# PIRSN_v1.net
KiCad netlist of a schematic drawn in EAGLE
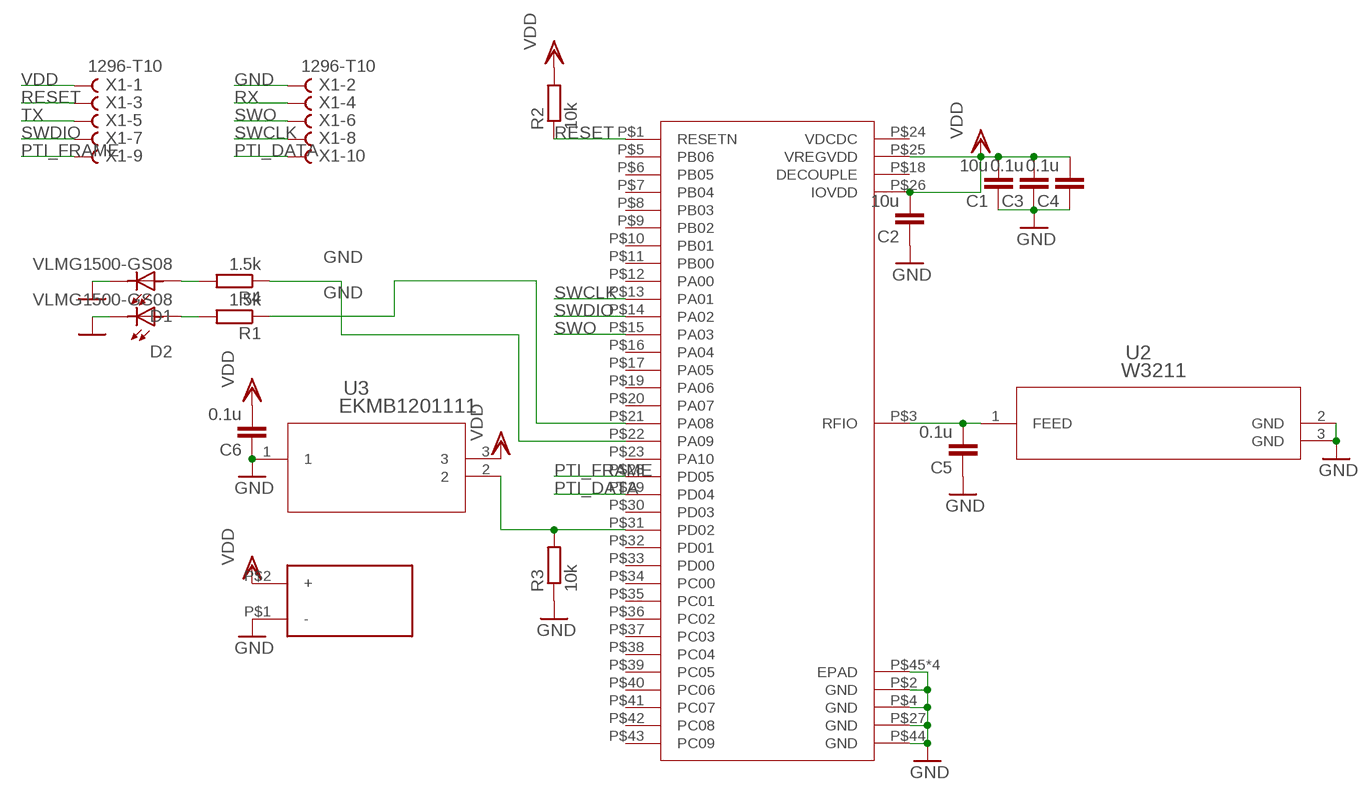
[diagram p0: schematic, sheet 1]

(export (version "E")
  (design (tool "Eeschema 10.0.6"))
  (components
    (comp (ref "C1")
      (value "10u")
      (footprint "eagle-import:C0603R")
      (libsource (lib "eagle-import") (part "CC0603R"))
    )
    (comp (ref "C2")
      (value "10u")
      (footprint "eagle-import:C0603R")
      (libsource (lib "eagle-import") (part "CC0603R"))
    )
    (comp (ref "C3")
      (value "0.1u")
      (footprint "eagle-import:C0402")
      (libsource (lib "eagle-import") (part "CC0402"))
    )
    (comp (ref "C4")
      (value "0.1u")
      (footprint "eagle-import:C0402")
      (libsource (lib "eagle-import") (part "CC0402"))
    )
    (comp (ref "C5")
      (value "0.1u")
      (footprint "eagle-import:C0402")
      (libsource (lib "eagle-import") (part "CC0402"))
    )
    (comp (ref "C6")
      (value "0.1u")
      (footprint "eagle-import:C0402")
      (libsource (lib "eagle-import") (part "CC0402"))
    )
    (comp (ref "D1")
      (value "VLMG1500-GS08")
      (footprint "eagle-import:LEDC1005X35N")
      (fields (field (name "MF") "Vishay"))
      (libsource (lib "eagle-import") (part "VLMG1500-GS08"))
    )
    (comp (ref "D2")
      (value "VLMG1500-GS08")
      (footprint "eagle-import:LEDC1005X35N")
      (fields (field (name "MF") "Vishay"))
      (libsource (lib "eagle-import") (part "VLMG1500-GS08"))
    )
    (comp (ref "R1")
      (value "1.5k")
      (footprint "eagle-import:R0402")
      (libsource (lib "eagle-import") (part "RR0402"))
    )
    (comp (ref "R2")
      (value "10k")
      (footprint "eagle-import:R0402")
      (libsource (lib "eagle-import") (part "RR0402"))
    )
    (comp (ref "R3")
      (value "10k")
      (footprint "eagle-import:R0402")
      (libsource (lib "eagle-import") (part "RR0402"))
    )
    (comp (ref "R4")
      (value "1.5k")
      (footprint "eagle-import:R0402")
      (libsource (lib "eagle-import") (part "RR0402"))
    )
    (comp (ref "U$1")
      (value "ZGM230S")
      (footprint "eagle-import:ZGM230S")
      (libsource (lib "eagle-import") (part "ZGM230S"))
    )
    (comp (ref "U$2")
      (value "BS-24R")
      (footprint "eagle-import:BS-24")
      (libsource (lib "eagle-import") (part "BS-24R"))
    )
    (comp (ref "U2")
      (value "W3211")
      (footprint "eagle-import:CHIP_3211_PUL")
      (fields (field (name "COPYRIGHT") "Copyright (C) 2022 Ultra Librarian. All rights reserved."))
      (libsource (lib "eagle-import") (part "W3211"))
    )
    (comp (ref "U3")
      (value "EKMB1201111")
      (footprint "eagle-import:SENSOR_B1201111_PAN")
      (fields (field (name "COPYRIGHT") "Copyright (C) 2022 Ultra Librarian. All rights reserved."))
      (libsource (lib "eagle-import") (part "EKMB1201111"))
    )
    (comp (ref "X1")
      (value "1296-T10")
      (footprint "eagle-import:1296-10")
      (libsource (lib "eagle-import") (part "1296-T10"))
    )
  )
  (nets
    (net (code "1") (name "/PTI_DATA") (class "Default")
      (node (ref "U$1") (pin "P$29") (pinfunction "PD04_P$29") (pintype "bidirectional"))
      (node (ref "X1") (pin "10") (pinfunction "B_10") (pintype "passive"))
    )
    (net (code "2") (name "/PTI_FRAME") (class "Default")
      (node (ref "U$1") (pin "P$28") (pinfunction "PD05_P$28") (pintype "bidirectional"))
      (node (ref "X1") (pin "9") (pinfunction "B_9") (pintype "passive"))
    )
    (net (code "3") (name "/RESET") (class "Default")
      (node (ref "R2") (pin "1") (pinfunction "1_1") (pintype "passive"))
      (node (ref "U$1") (pin "P$1") (pinfunction "RESETN_P$1") (pintype "bidirectional"))
      (node (ref "X1") (pin "3") (pinfunction "B_3") (pintype "passive"))
    )
    (net (code "4") (name "/RX") (class "Default")
      (node (ref "X1") (pin "4") (pinfunction "B_4") (pintype "passive"))
    )
    (net (code "5") (name "/SWCLK") (class "Default")
      (node (ref "U$1") (pin "P$13") (pinfunction "PA01_P$13") (pintype "bidirectional"))
      (node (ref "X1") (pin "8") (pinfunction "B_8") (pintype "passive"))
    )
    (net (code "6") (name "/SWDIO") (class "Default")
      (node (ref "U$1") (pin "P$14") (pinfunction "PA02_P$14") (pintype "bidirectional"))
      (node (ref "X1") (pin "7") (pinfunction "B_7") (pintype "passive"))
    )
    (net (code "7") (name "/SWO") (class "Default")
      (node (ref "U$1") (pin "P$15") (pinfunction "PA03_P$15") (pintype "bidirectional"))
      (node (ref "X1") (pin "6") (pinfunction "B_6") (pintype "passive"))
    )
    (net (code "8") (name "/TX") (class "Default")
      (node (ref "X1") (pin "5") (pinfunction "B_5") (pintype "passive"))
    )
    (net (code "9") (name "GND") (class "Default")
      (node (ref "C1") (pin "1") (pinfunction "1_1") (pintype "passive"))
      (node (ref "C2") (pin "1") (pinfunction "1_1") (pintype "passive"))
      (node (ref "C3") (pin "1") (pinfunction "1_1") (pintype "passive"))
      (node (ref "C4") (pin "1") (pinfunction "1_1") (pintype "passive"))
      (node (ref "C5") (pin "1") (pinfunction "1_1") (pintype "passive"))
      (node (ref "C6") (pin "1") (pinfunction "1_1") (pintype "passive"))
      (node (ref "D1") (pin "2") (pinfunction "2_2") (pintype "passive"))
      (node (ref "D2") (pin "2") (pinfunction "2_2") (pintype "passive"))
      (node (ref "R3") (pin "1") (pinfunction "1_1") (pintype "passive"))
      (node (ref "U$1") (pin "P$2") (pinfunction "GND_P$2") (pintype "bidirectional"))
      (node (ref "U$1") (pin "P$27") (pinfunction "GND_P$27") (pintype "bidirectional"))
      (node (ref "U$1") (pin "P$4") (pinfunction "GND_P$4") (pintype "bidirectional"))
      (node (ref "U$1") (pin "P$44") (pinfunction "GND_P$44") (pintype "bidirectional"))
      (node (ref "U$1") (pin "P$45") (pinfunction "EPAD_P$45") (pintype "bidirectional"))
      (node (ref "U$1") (pin "P$46") (pinfunction "EPAD_P$46") (pintype "bidirectional"))
      (node (ref "U$1") (pin "P$47") (pinfunction "EPAD_P$47") (pintype "bidirectional"))
      (node (ref "U$1") (pin "P$48") (pinfunction "EPAD_P$48") (pintype "bidirectional"))
      (node (ref "U$2") (pin "P$1") (pinfunction "-_P$1") (pintype "bidirectional"))
      (node (ref "U2") (pin "2") (pinfunction "GND_2") (pintype "passive"))
      (node (ref "U2") (pin "3") (pinfunction "GND_3") (pintype "passive"))
      (node (ref "U3") (pin "1") (pinfunction "1_1") (pintype "passive"))
      (node (ref "X1") (pin "2") (pinfunction "B_2") (pintype "passive"))
    )
    (net (code "10") (name "Net-(D1-Pad1)") (class "Default")
      (node (ref "D1") (pin "1") (pinfunction "1_1") (pintype "passive"))
      (node (ref "R4") (pin "2") (pinfunction "2_2") (pintype "passive"))
    )
    (net (code "11") (name "Net-(D2-Pad1)") (class "Default")
      (node (ref "D2") (pin "1") (pinfunction "1_1") (pintype "passive"))
      (node (ref "R1") (pin "2") (pinfunction "2_2") (pintype "passive"))
    )
    (net (code "12") (name "Net-(U$1-PA08)") (class "Default")
      (node (ref "R1") (pin "1") (pinfunction "1_1") (pintype "passive"))
      (node (ref "U$1") (pin "P$21") (pinfunction "PA08_P$21") (pintype "bidirectional"))
    )
    (net (code "13") (name "Net-(U$1-PA09)") (class "Default")
      (node (ref "R4") (pin "1") (pinfunction "1_1") (pintype "passive"))
      (node (ref "U$1") (pin "P$22") (pinfunction "PA09_P$22") (pintype "bidirectional"))
    )
    (net (code "14") (name "Net-(U$1-PD02)") (class "Default")
      (node (ref "R3") (pin "2") (pinfunction "2_2") (pintype "passive"))
      (node (ref "U$1") (pin "P$31") (pinfunction "PD02_P$31") (pintype "bidirectional"))
      (node (ref "U3") (pin "2") (pinfunction "2_2") (pintype "passive"))
    )
    (net (code "15") (name "Net-(U$1-RFIO)") (class "Default")
      (node (ref "C5") (pin "2") (pinfunction "2_2") (pintype "passive"))
      (node (ref "U$1") (pin "P$3") (pinfunction "RFIO_P$3") (pintype "bidirectional"))
      (node (ref "U2") (pin "1") (pinfunction "FEED_1") (pintype "passive"))
    )
    (net (code "16") (name "VDD") (class "Default")
      (node (ref "C1") (pin "2") (pinfunction "2_2") (pintype "passive"))
      (node (ref "C2") (pin "2") (pinfunction "2_2") (pintype "passive"))
      (node (ref "C3") (pin "2") (pinfunction "2_2") (pintype "passive"))
      (node (ref "C4") (pin "2") (pinfunction "2_2") (pintype "passive"))
      (node (ref "C6") (pin "2") (pinfunction "2_2") (pintype "passive"))
      (node (ref "R2") (pin "2") (pinfunction "2_2") (pintype "passive"))
      (node (ref "U$1") (pin "P$25") (pinfunction "VREGVDD_P$25") (pintype "bidirectional"))
      (node (ref "U$1") (pin "P$26") (pinfunction "IOVDD_P$26") (pintype "bidirectional"))
      (node (ref "U$2") (pin "P$2") (pinfunction "+_P$2") (pintype "bidirectional"))
      (node (ref "U3") (pin "3") (pinfunction "3_3") (pintype "passive"))
      (node (ref "X1") (pin "1") (pinfunction "B_1") (pintype "passive"))
    )
    (net (code "17") (name "unconnected-(U$1-DECOUPLE-PadP$18)") (class "Default")
      (node (ref "U$1") (pin "P$18") (pinfunction "DECOUPLE_P$18") (pintype "bidirectional"))
    )
    (net (code "18") (name "unconnected-(U$1-PA00-PadP$12)") (class "Default")
      (node (ref "U$1") (pin "P$12") (pinfunction "PA00_P$12") (pintype "bidirectional"))
    )
    (net (code "19") (name "unconnected-(U$1-PA04-PadP$16)") (class "Default")
      (node (ref "U$1") (pin "P$16") (pinfunction "PA04_P$16") (pintype "bidirectional"))
    )
    (net (code "20") (name "unconnected-(U$1-PA05-PadP$17)") (class "Default")
      (node (ref "U$1") (pin "P$17") (pinfunction "PA05_P$17") (pintype "bidirectional"))
    )
    (net (code "21") (name "unconnected-(U$1-PA06-PadP$19)") (class "Default")
      (node (ref "U$1") (pin "P$19") (pinfunction "PA06_P$19") (pintype "bidirectional"))
    )
    (net (code "22") (name "unconnected-(U$1-PA07-PadP$20)") (class "Default")
      (node (ref "U$1") (pin "P$20") (pinfunction "PA07_P$20") (pintype "bidirectional"))
    )
    (net (code "23") (name "unconnected-(U$1-PA10-PadP$23)") (class "Default")
      (node (ref "U$1") (pin "P$23") (pinfunction "PA10_P$23") (pintype "bidirectional"))
    )
    (net (code "24") (name "unconnected-(U$1-PB00-PadP$11)") (class "Default")
      (node (ref "U$1") (pin "P$11") (pinfunction "PB00_P$11") (pintype "bidirectional"))
    )
    (net (code "25") (name "unconnected-(U$1-PB01-PadP$10)") (class "Default")
      (node (ref "U$1") (pin "P$10") (pinfunction "PB01_P$10") (pintype "bidirectional"))
    )
    (net (code "26") (name "unconnected-(U$1-PB02-PadP$9)") (class "Default")
      (node (ref "U$1") (pin "P$9") (pinfunction "PB02_P$9") (pintype "bidirectional"))
    )
    (net (code "27") (name "unconnected-(U$1-PB03-PadP$8)") (class "Default")
      (node (ref "U$1") (pin "P$8") (pinfunction "PB03_P$8") (pintype "bidirectional"))
    )
    (net (code "28") (name "unconnected-(U$1-PB04-PadP$7)") (class "Default")
      (node (ref "U$1") (pin "P$7") (pinfunction "PB04_P$7") (pintype "bidirectional"))
    )
    (net (code "29") (name "unconnected-(U$1-PB05-PadP$6)") (class "Default")
      (node (ref "U$1") (pin "P$6") (pinfunction "PB05_P$6") (pintype "bidirectional"))
    )
    (net (code "30") (name "unconnected-(U$1-PB06-PadP$5)") (class "Default")
      (node (ref "U$1") (pin "P$5") (pinfunction "PB06_P$5") (pintype "bidirectional"))
    )
    (net (code "31") (name "unconnected-(U$1-PC00-PadP$34)") (class "Default")
      (node (ref "U$1") (pin "P$34") (pinfunction "PC00_P$34") (pintype "bidirectional"))
    )
    (net (code "32") (name "unconnected-(U$1-PC01-PadP$35)") (class "Default")
      (node (ref "U$1") (pin "P$35") (pinfunction "PC01_P$35") (pintype "bidirectional"))
    )
    (net (code "33") (name "unconnected-(U$1-PC02-PadP$36)") (class "Default")
      (node (ref "U$1") (pin "P$36") (pinfunction "PC02_P$36") (pintype "bidirectional"))
    )
    (net (code "34") (name "unconnected-(U$1-PC03-PadP$37)") (class "Default")
      (node (ref "U$1") (pin "P$37") (pinfunction "PC03_P$37") (pintype "bidirectional"))
    )
    (net (code "35") (name "unconnected-(U$1-PC04-PadP$38)") (class "Default")
      (node (ref "U$1") (pin "P$38") (pinfunction "PC04_P$38") (pintype "bidirectional"))
    )
    (net (code "36") (name "unconnected-(U$1-PC05-PadP$39)") (class "Default")
      (node (ref "U$1") (pin "P$39") (pinfunction "PC05_P$39") (pintype "bidirectional"))
    )
    (net (code "37") (name "unconnected-(U$1-PC06-PadP$40)") (class "Default")
      (node (ref "U$1") (pin "P$40") (pinfunction "PC06_P$40") (pintype "bidirectional"))
    )
    (net (code "38") (name "unconnected-(U$1-PC07-PadP$41)") (class "Default")
      (node (ref "U$1") (pin "P$41") (pinfunction "PC07_P$41") (pintype "bidirectional"))
    )
    (net (code "39") (name "unconnected-(U$1-PC08-PadP$42)") (class "Default")
      (node (ref "U$1") (pin "P$42") (pinfunction "PC08_P$42") (pintype "bidirectional"))
    )
    (net (code "40") (name "unconnected-(U$1-PC09-PadP$43)") (class "Default")
      (node (ref "U$1") (pin "P$43") (pinfunction "PC09_P$43") (pintype "bidirectional"))
    )
    (net (code "41") (name "unconnected-(U$1-PD00-PadP$33)") (class "Default")
      (node (ref "U$1") (pin "P$33") (pinfunction "PD00_P$33") (pintype "bidirectional"))
    )
    (net (code "42") (name "unconnected-(U$1-PD01-PadP$32)") (class "Default")
      (node (ref "U$1") (pin "P$32") (pinfunction "PD01_P$32") (pintype "bidirectional"))
    )
    (net (code "43") (name "unconnected-(U$1-PD03-PadP$30)") (class "Default")
      (node (ref "U$1") (pin "P$30") (pinfunction "PD03_P$30") (pintype "bidirectional"))
    )
    (net (code "44") (name "unconnected-(U$1-VDCDC-PadP$24)") (class "Default")
      (node (ref "U$1") (pin "P$24") (pinfunction "VDCDC_P$24") (pintype "bidirectional"))
    )
  )
)
